# motors.net
KiCad netlist of a schematic drawn in EAGLE
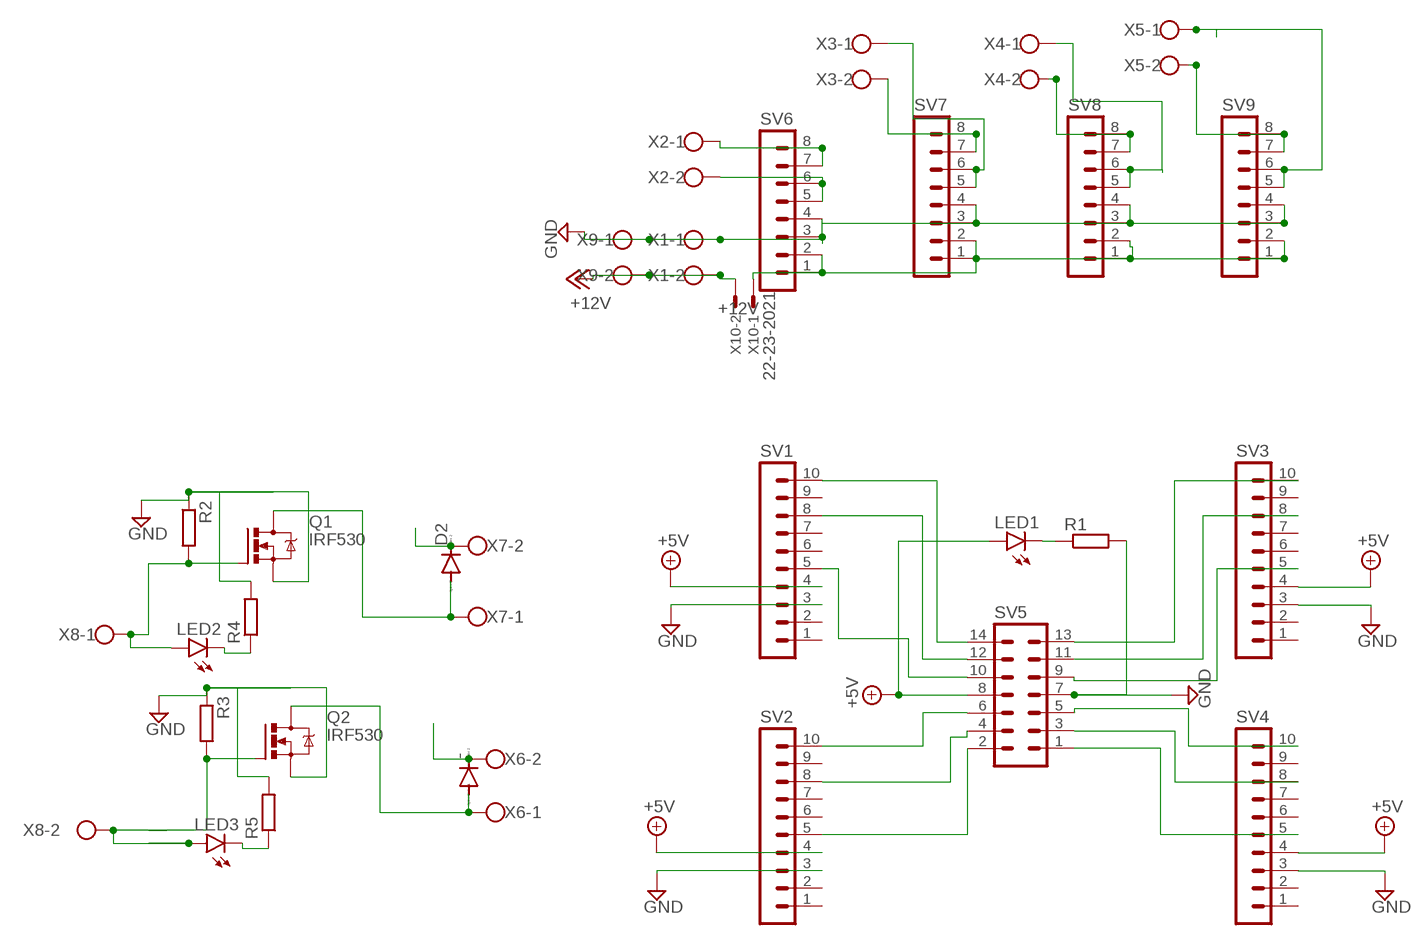
[diagram p0: schematic, sheet 1]

(export (version "E")
  (design (tool "Eeschema 10.0.6"))
  (components
    (comp (ref "-")
      (value "DIODE-DO41-7.6")
      (footprint "eagle-import:DO41-7.6")
      (libsource (lib "eagle-import") (part "DIODE-DO41-7.6"))
    )
    (comp (ref "D2")
      (value "DIODE-DO41-7.6")
      (footprint "eagle-import:DO41-7.6")
      (libsource (lib "eagle-import") (part "DIODE-DO41-7.6"))
    )
    (comp (ref "LED1")
      (value "LED5MM")
      (footprint "eagle-import:LED5MM")
      (libsource (lib "eagle-import") (part "LED5MM"))
    )
    (comp (ref "LED2")
      (value "LED5MM")
      (footprint "eagle-import:LED5MM")
      (libsource (lib "eagle-import") (part "LED5MM"))
    )
    (comp (ref "LED3")
      (value "LED5MM")
      (footprint "eagle-import:LED5MM")
      (libsource (lib "eagle-import") (part "LED5MM"))
    )
    (comp (ref "Q1")
      (value "IRF530")
      (footprint "eagle-import:TO220BV")
      (libsource (lib "eagle-import") (part "IRF530"))
    )
    (comp (ref "Q2")
      (value "IRF530")
      (footprint "eagle-import:TO220BV")
      (libsource (lib "eagle-import") (part "IRF530"))
    )
    (comp (ref "R1")
      (value "R-EU_0207/7")
      (footprint "eagle-import:0207_7")
      (libsource (lib "eagle-import") (part "R-EU_0207/7"))
    )
    (comp (ref "R2")
      (value "R-EU_0207/7")
      (footprint "eagle-import:0207_7")
      (libsource (lib "eagle-import") (part "R-EU_0207/7"))
    )
    (comp (ref "R3")
      (value "R-EU_0207/7")
      (footprint "eagle-import:0207_7")
      (libsource (lib "eagle-import") (part "R-EU_0207/7"))
    )
    (comp (ref "R4")
      (value "R-EU_0207/7")
      (footprint "eagle-import:0207_7")
      (libsource (lib "eagle-import") (part "R-EU_0207/7"))
    )
    (comp (ref "R5")
      (value "R-EU_0207/7")
      (footprint "eagle-import:0207_7")
      (libsource (lib "eagle-import") (part "R-EU_0207/7"))
    )
    (comp (ref "SV1")
      (value "MA10-1")
      (footprint "eagle-import:MA10-1")
      (libsource (lib "eagle-import") (part "MA10-1"))
    )
    (comp (ref "SV2")
      (value "MA10-1")
      (footprint "eagle-import:MA10-1")
      (libsource (lib "eagle-import") (part "MA10-1"))
    )
    (comp (ref "SV3")
      (value "MA10-1")
      (footprint "eagle-import:MA10-1")
      (libsource (lib "eagle-import") (part "MA10-1"))
    )
    (comp (ref "SV4")
      (value "MA10-1")
      (footprint "eagle-import:MA10-1")
      (libsource (lib "eagle-import") (part "MA10-1"))
    )
    (comp (ref "SV5")
      (value "MA07-2")
      (footprint "eagle-import:MA07-2")
      (libsource (lib "eagle-import") (part "MA07-2"))
    )
    (comp (ref "SV6")
      (value "MA08-1")
      (footprint "eagle-import:MA08-1")
      (libsource (lib "eagle-import") (part "MA08-1"))
    )
    (comp (ref "SV7")
      (value "MA08-1")
      (footprint "eagle-import:MA08-1")
      (libsource (lib "eagle-import") (part "MA08-1"))
    )
    (comp (ref "SV8")
      (value "MA08-1")
      (footprint "eagle-import:MA08-1")
      (libsource (lib "eagle-import") (part "MA08-1"))
    )
    (comp (ref "SV9")
      (value "MA08-1")
      (footprint "eagle-import:MA08-1")
      (libsource (lib "eagle-import") (part "MA08-1"))
    )
    (comp (ref "X1")
      (value "W237-102")
      (footprint "eagle-import:W237-102")
      (fields (field (name "MPN") "237-102"))
      (libsource (lib "eagle-import") (part "W237-102"))
    )
    (comp (ref "X2")
      (value "W237-102")
      (footprint "eagle-import:W237-102")
      (fields (field (name "MPN") "237-102"))
      (libsource (lib "eagle-import") (part "W237-102"))
    )
    (comp (ref "X3")
      (value "W237-102")
      (footprint "eagle-import:W237-102")
      (fields (field (name "MPN") "237-102"))
      (libsource (lib "eagle-import") (part "W237-102"))
    )
    (comp (ref "X4")
      (value "W237-102")
      (footprint "eagle-import:W237-102")
      (fields (field (name "MPN") "237-102"))
      (libsource (lib "eagle-import") (part "W237-102"))
    )
    (comp (ref "X5")
      (value "W237-102")
      (footprint "eagle-import:W237-102")
      (fields (field (name "MPN") "237-102"))
      (libsource (lib "eagle-import") (part "W237-102"))
    )
    (comp (ref "X6")
      (value "W237-102")
      (footprint "eagle-import:W237-102")
      (fields (field (name "MPN") "237-102"))
      (libsource (lib "eagle-import") (part "W237-102"))
    )
    (comp (ref "X7")
      (value "W237-102")
      (footprint "eagle-import:W237-102")
      (fields (field (name "MPN") "237-102"))
      (libsource (lib "eagle-import") (part "W237-102"))
    )
    (comp (ref "X8")
      (value "W237-102")
      (footprint "eagle-import:W237-102")
      (fields (field (name "MPN") "237-102"))
      (libsource (lib "eagle-import") (part "W237-102"))
    )
    (comp (ref "X9")
      (value "W237-102")
      (footprint "eagle-import:W237-102")
      (fields (field (name "MPN") "237-102"))
      (libsource (lib "eagle-import") (part "W237-102"))
    )
    (comp (ref "X10")
      (value "22-23-2021")
      (footprint "eagle-import:22-23-2021")
      (fields (field (name "MF") "MOLEX"))
      (libsource (lib "eagle-import") (part "22-23-2021"))
    )
  )
  (nets
    (net (code "1") (name "+5V") (class "Default")
      (node (ref "LED1") (pin "A") (pinfunction "A_A") (pintype "passive"))
      (node (ref "SV1") (pin "4") (pinfunction "4_4") (pintype "passive"))
      (node (ref "SV2") (pin "4") (pinfunction "4_4") (pintype "passive"))
      (node (ref "SV3") (pin "4") (pinfunction "4_4") (pintype "passive"))
      (node (ref "SV4") (pin "4") (pinfunction "4_4") (pintype "passive"))
      (node (ref "SV5") (pin "8") (pinfunction "8_8") (pintype "passive"))
    )
    (net (code "2") (name "+12V") (class "Default")
      (node (ref "X1") (pin "2") (pinfunction "KL_2") (pintype "passive"))
      (node (ref "X10") (pin "2") (pinfunction "S_2") (pintype "passive"))
      (node (ref "X9") (pin "2") (pinfunction "KL_2") (pintype "passive"))
    )
    (net (code "3") (name "/N$22") (class "Default")
      (node (ref "-") (pin "C") (pinfunction "C_C") (pintype "passive"))
      (node (ref "D2") (pin "C") (pinfunction "C_C") (pintype "passive"))
      (node (ref "SV6") (pin "1") (pinfunction "1_1") (pintype "passive"))
      (node (ref "SV6") (pin "2") (pinfunction "2_2") (pintype "passive"))
      (node (ref "SV7") (pin "1") (pinfunction "1_1") (pintype "passive"))
      (node (ref "SV7") (pin "2") (pinfunction "2_2") (pintype "passive"))
      (node (ref "SV8") (pin "1") (pinfunction "1_1") (pintype "passive"))
      (node (ref "SV8") (pin "2") (pinfunction "2_2") (pintype "passive"))
      (node (ref "SV9") (pin "1") (pinfunction "1_1") (pintype "passive"))
      (node (ref "SV9") (pin "2") (pinfunction "2_2") (pintype "passive"))
      (node (ref "X10") (pin "1") (pinfunction "S_1") (pintype "passive"))
      (node (ref "X6") (pin "2") (pinfunction "KL_2") (pintype "passive"))
      (node (ref "X7") (pin "2") (pinfunction "KL_2") (pintype "passive"))
    )
    (net (code "4") (name "GND") (class "Default")
      (node (ref "Q1") (pin "S") (pinfunction "S_S") (pintype "passive"))
      (node (ref "Q2") (pin "S") (pinfunction "S_S") (pintype "passive"))
      (node (ref "R1") (pin "2") (pinfunction "2_2") (pintype "passive"))
      (node (ref "R2") (pin "1") (pinfunction "1_1") (pintype "passive"))
      (node (ref "R3") (pin "1") (pinfunction "1_1") (pintype "passive"))
      (node (ref "R4") (pin "2") (pinfunction "2_2") (pintype "passive"))
      (node (ref "R5") (pin "2") (pinfunction "2_2") (pintype "passive"))
      (node (ref "SV1") (pin "3") (pinfunction "3_3") (pintype "passive"))
      (node (ref "SV2") (pin "3") (pinfunction "3_3") (pintype "passive"))
      (node (ref "SV3") (pin "3") (pinfunction "3_3") (pintype "passive"))
      (node (ref "SV4") (pin "3") (pinfunction "3_3") (pintype "passive"))
      (node (ref "SV5") (pin "7") (pinfunction "7_7") (pintype "passive"))
      (node (ref "SV6") (pin "3") (pinfunction "3_3") (pintype "passive"))
      (node (ref "SV6") (pin "4") (pinfunction "4_4") (pintype "passive"))
      (node (ref "SV7") (pin "3") (pinfunction "3_3") (pintype "passive"))
      (node (ref "SV7") (pin "4") (pinfunction "4_4") (pintype "passive"))
      (node (ref "SV8") (pin "3") (pinfunction "3_3") (pintype "passive"))
      (node (ref "SV8") (pin "4") (pinfunction "4_4") (pintype "passive"))
      (node (ref "SV9") (pin "3") (pinfunction "3_3") (pintype "passive"))
      (node (ref "SV9") (pin "4") (pinfunction "4_4") (pintype "passive"))
      (node (ref "X1") (pin "1") (pinfunction "KL_1") (pintype "passive"))
      (node (ref "X9") (pin "1") (pinfunction "KL_1") (pintype "passive"))
    )
    (net (code "5") (name "Net-(LED1-C)") (class "Default")
      (node (ref "LED1") (pin "K") (pinfunction "C_K") (pintype "passive"))
      (node (ref "R1") (pin "1") (pinfunction "1_1") (pintype "passive"))
    )
    (net (code "6") (name "Net-(LED2-C)") (class "Default")
      (node (ref "LED2") (pin "K") (pinfunction "C_K") (pintype "passive"))
      (node (ref "R4") (pin "1") (pinfunction "1_1") (pintype "passive"))
    )
    (net (code "7") (name "Net-(LED3-C)") (class "Default")
      (node (ref "LED3") (pin "K") (pinfunction "C_K") (pintype "passive"))
      (node (ref "R5") (pin "1") (pinfunction "1_1") (pintype "passive"))
    )
    (net (code "8") (name "Net-(SV1-Pad5)") (class "Default")
      (node (ref "SV1") (pin "5") (pinfunction "5_5") (pintype "passive"))
      (node (ref "SV5") (pin "10") (pinfunction "10_10") (pintype "passive"))
    )
    (net (code "9") (name "Net-(SV1-Pad8)") (class "Default")
      (node (ref "SV1") (pin "8") (pinfunction "8_8") (pintype "passive"))
      (node (ref "SV5") (pin "12") (pinfunction "12_12") (pintype "passive"))
    )
    (net (code "10") (name "Net-(SV1-Pad10)") (class "Default")
      (node (ref "SV1") (pin "10") (pinfunction "10_10") (pintype "passive"))
      (node (ref "SV5") (pin "14") (pinfunction "14_14") (pintype "passive"))
    )
    (net (code "11") (name "Net-(SV2-Pad5)") (class "Default")
      (node (ref "SV2") (pin "5") (pinfunction "5_5") (pintype "passive"))
      (node (ref "SV5") (pin "2") (pinfunction "2_2") (pintype "passive"))
    )
    (net (code "12") (name "Net-(SV2-Pad8)") (class "Default")
      (node (ref "SV2") (pin "8") (pinfunction "8_8") (pintype "passive"))
      (node (ref "SV5") (pin "4") (pinfunction "4_4") (pintype "passive"))
    )
    (net (code "13") (name "Net-(SV2-Pad10)") (class "Default")
      (node (ref "SV2") (pin "10") (pinfunction "10_10") (pintype "passive"))
      (node (ref "SV5") (pin "6") (pinfunction "6_6") (pintype "passive"))
    )
    (net (code "14") (name "Net-(SV3-Pad5)") (class "Default")
      (node (ref "SV3") (pin "5") (pinfunction "5_5") (pintype "passive"))
      (node (ref "SV5") (pin "9") (pinfunction "9_9") (pintype "passive"))
    )
    (net (code "15") (name "Net-(SV3-Pad8)") (class "Default")
      (node (ref "SV3") (pin "8") (pinfunction "8_8") (pintype "passive"))
      (node (ref "SV5") (pin "11") (pinfunction "11_11") (pintype "passive"))
    )
    (net (code "16") (name "Net-(SV3-Pad10)") (class "Default")
      (node (ref "SV3") (pin "10") (pinfunction "10_10") (pintype "passive"))
      (node (ref "SV5") (pin "13") (pinfunction "13_13") (pintype "passive"))
    )
    (net (code "17") (name "Net-(SV4-Pad5)") (class "Default")
      (node (ref "SV4") (pin "5") (pinfunction "5_5") (pintype "passive"))
      (node (ref "SV5") (pin "1") (pinfunction "1_1") (pintype "passive"))
    )
    (net (code "18") (name "Net-(SV4-Pad8)") (class "Default")
      (node (ref "SV4") (pin "8") (pinfunction "8_8") (pintype "passive"))
      (node (ref "SV5") (pin "3") (pinfunction "3_3") (pintype "passive"))
    )
    (net (code "19") (name "Net-(SV4-Pad10)") (class "Default")
      (node (ref "SV4") (pin "10") (pinfunction "10_10") (pintype "passive"))
      (node (ref "SV5") (pin "5") (pinfunction "5_5") (pintype "passive"))
    )
    (net (code "20") (name "Net-(X2A-KL)") (class "Default")
      (node (ref "SV6") (pin "7") (pinfunction "7_7") (pintype "passive"))
      (node (ref "SV6") (pin "8") (pinfunction "8_8") (pintype "passive"))
      (node (ref "X2") (pin "1") (pinfunction "KL_1") (pintype "passive"))
    )
    (net (code "21") (name "Net-(X2B-KL)") (class "Default")
      (node (ref "SV6") (pin "5") (pinfunction "5_5") (pintype "passive"))
      (node (ref "SV6") (pin "6") (pinfunction "6_6") (pintype "passive"))
      (node (ref "X2") (pin "2") (pinfunction "KL_2") (pintype "passive"))
    )
    (net (code "22") (name "Net-(X3A-KL)") (class "Default")
      (node (ref "SV7") (pin "5") (pinfunction "5_5") (pintype "passive"))
      (node (ref "SV7") (pin "6") (pinfunction "6_6") (pintype "passive"))
      (node (ref "X3") (pin "1") (pinfunction "KL_1") (pintype "passive"))
    )
    (net (code "23") (name "Net-(X3B-KL)") (class "Default")
      (node (ref "SV7") (pin "7") (pinfunction "7_7") (pintype "passive"))
      (node (ref "SV7") (pin "8") (pinfunction "8_8") (pintype "passive"))
      (node (ref "X3") (pin "2") (pinfunction "KL_2") (pintype "passive"))
    )
    (net (code "24") (name "Net-(X4A-KL)") (class "Default")
      (node (ref "SV8") (pin "5") (pinfunction "5_5") (pintype "passive"))
      (node (ref "SV8") (pin "6") (pinfunction "6_6") (pintype "passive"))
      (node (ref "X4") (pin "1") (pinfunction "KL_1") (pintype "passive"))
    )
    (net (code "25") (name "Net-(X4B-KL)") (class "Default")
      (node (ref "SV8") (pin "7") (pinfunction "7_7") (pintype "passive"))
      (node (ref "SV8") (pin "8") (pinfunction "8_8") (pintype "passive"))
      (node (ref "X4") (pin "2") (pinfunction "KL_2") (pintype "passive"))
    )
    (net (code "26") (name "Net-(X5A-KL)") (class "Default")
      (node (ref "SV9") (pin "5") (pinfunction "5_5") (pintype "passive"))
      (node (ref "SV9") (pin "6") (pinfunction "6_6") (pintype "passive"))
      (node (ref "X5") (pin "1") (pinfunction "KL_1") (pintype "passive"))
    )
    (net (code "27") (name "Net-(X5B-KL)") (class "Default")
      (node (ref "SV9") (pin "7") (pinfunction "7_7") (pintype "passive"))
      (node (ref "SV9") (pin "8") (pinfunction "8_8") (pintype "passive"))
      (node (ref "X5") (pin "2") (pinfunction "KL_2") (pintype "passive"))
    )
    (net (code "28") (name "Net-(X6A-KL)") (class "Default")
      (node (ref "-") (pin "A") (pinfunction "A_A") (pintype "passive"))
      (node (ref "Q2") (pin "D") (pinfunction "D_D") (pintype "passive"))
      (node (ref "X6") (pin "1") (pinfunction "KL_1") (pintype "passive"))
    )
    (net (code "29") (name "Net-(X7A-KL)") (class "Default")
      (node (ref "D2") (pin "A") (pinfunction "A_A") (pintype "passive"))
      (node (ref "Q1") (pin "D") (pinfunction "D_D") (pintype "passive"))
      (node (ref "X7") (pin "1") (pinfunction "KL_1") (pintype "passive"))
    )
    (net (code "30") (name "Net-(X8A-KL)") (class "Default")
      (node (ref "LED2") (pin "A") (pinfunction "A_A") (pintype "passive"))
      (node (ref "Q1") (pin "G") (pinfunction "G_G") (pintype "passive"))
      (node (ref "R2") (pin "2") (pinfunction "2_2") (pintype "passive"))
      (node (ref "X8") (pin "1") (pinfunction "KL_1") (pintype "passive"))
    )
    (net (code "31") (name "Net-(X8B-KL)") (class "Default")
      (node (ref "LED3") (pin "A") (pinfunction "A_A") (pintype "passive"))
      (node (ref "Q2") (pin "G") (pinfunction "G_G") (pintype "passive"))
      (node (ref "R3") (pin "2") (pinfunction "2_2") (pintype "passive"))
      (node (ref "X8") (pin "2") (pinfunction "KL_2") (pintype "passive"))
    )
    (net (code "32") (name "unconnected-(SV1-Pad1)") (class "Default")
      (node (ref "SV1") (pin "1") (pinfunction "1_1") (pintype "passive"))
    )
    (net (code "33") (name "unconnected-(SV1-Pad2)") (class "Default")
      (node (ref "SV1") (pin "2") (pinfunction "2_2") (pintype "passive"))
    )
    (net (code "34") (name "unconnected-(SV1-Pad6)") (class "Default")
      (node (ref "SV1") (pin "6") (pinfunction "6_6") (pintype "passive"))
    )
    (net (code "35") (name "unconnected-(SV1-Pad7)") (class "Default")
      (node (ref "SV1") (pin "7") (pinfunction "7_7") (pintype "passive"))
    )
    (net (code "36") (name "unconnected-(SV1-Pad9)") (class "Default")
      (node (ref "SV1") (pin "9") (pinfunction "9_9") (pintype "passive"))
    )
    (net (code "37") (name "unconnected-(SV2-Pad1)") (class "Default")
      (node (ref "SV2") (pin "1") (pinfunction "1_1") (pintype "passive"))
    )
    (net (code "38") (name "unconnected-(SV2-Pad2)") (class "Default")
      (node (ref "SV2") (pin "2") (pinfunction "2_2") (pintype "passive"))
    )
    (net (code "39") (name "unconnected-(SV2-Pad6)") (class "Default")
      (node (ref "SV2") (pin "6") (pinfunction "6_6") (pintype "passive"))
    )
    (net (code "40") (name "unconnected-(SV2-Pad7)") (class "Default")
      (node (ref "SV2") (pin "7") (pinfunction "7_7") (pintype "passive"))
    )
    (net (code "41") (name "unconnected-(SV2-Pad9)") (class "Default")
      (node (ref "SV2") (pin "9") (pinfunction "9_9") (pintype "passive"))
    )
    (net (code "42") (name "unconnected-(SV3-Pad1)") (class "Default")
      (node (ref "SV3") (pin "1") (pinfunction "1_1") (pintype "passive"))
    )
    (net (code "43") (name "unconnected-(SV3-Pad2)") (class "Default")
      (node (ref "SV3") (pin "2") (pinfunction "2_2") (pintype "passive"))
    )
    (net (code "44") (name "unconnected-(SV3-Pad6)") (class "Default")
      (node (ref "SV3") (pin "6") (pinfunction "6_6") (pintype "passive"))
    )
    (net (code "45") (name "unconnected-(SV3-Pad7)") (class "Default")
      (node (ref "SV3") (pin "7") (pinfunction "7_7") (pintype "passive"))
    )
    (net (code "46") (name "unconnected-(SV3-Pad9)") (class "Default")
      (node (ref "SV3") (pin "9") (pinfunction "9_9") (pintype "passive"))
    )
    (net (code "47") (name "unconnected-(SV4-Pad1)") (class "Default")
      (node (ref "SV4") (pin "1") (pinfunction "1_1") (pintype "passive"))
    )
    (net (code "48") (name "unconnected-(SV4-Pad2)") (class "Default")
      (node (ref "SV4") (pin "2") (pinfunction "2_2") (pintype "passive"))
    )
    (net (code "49") (name "unconnected-(SV4-Pad6)") (class "Default")
      (node (ref "SV4") (pin "6") (pinfunction "6_6") (pintype "passive"))
    )
    (net (code "50") (name "unconnected-(SV4-Pad7)") (class "Default")
      (node (ref "SV4") (pin "7") (pinfunction "7_7") (pintype "passive"))
    )
    (net (code "51") (name "unconnected-(SV4-Pad9)") (class "Default")
      (node (ref "SV4") (pin "9") (pinfunction "9_9") (pintype "passive"))
    )
  )
)
